# dev-v1_0.net
KiCad netlist of a schematic drawn in EAGLE
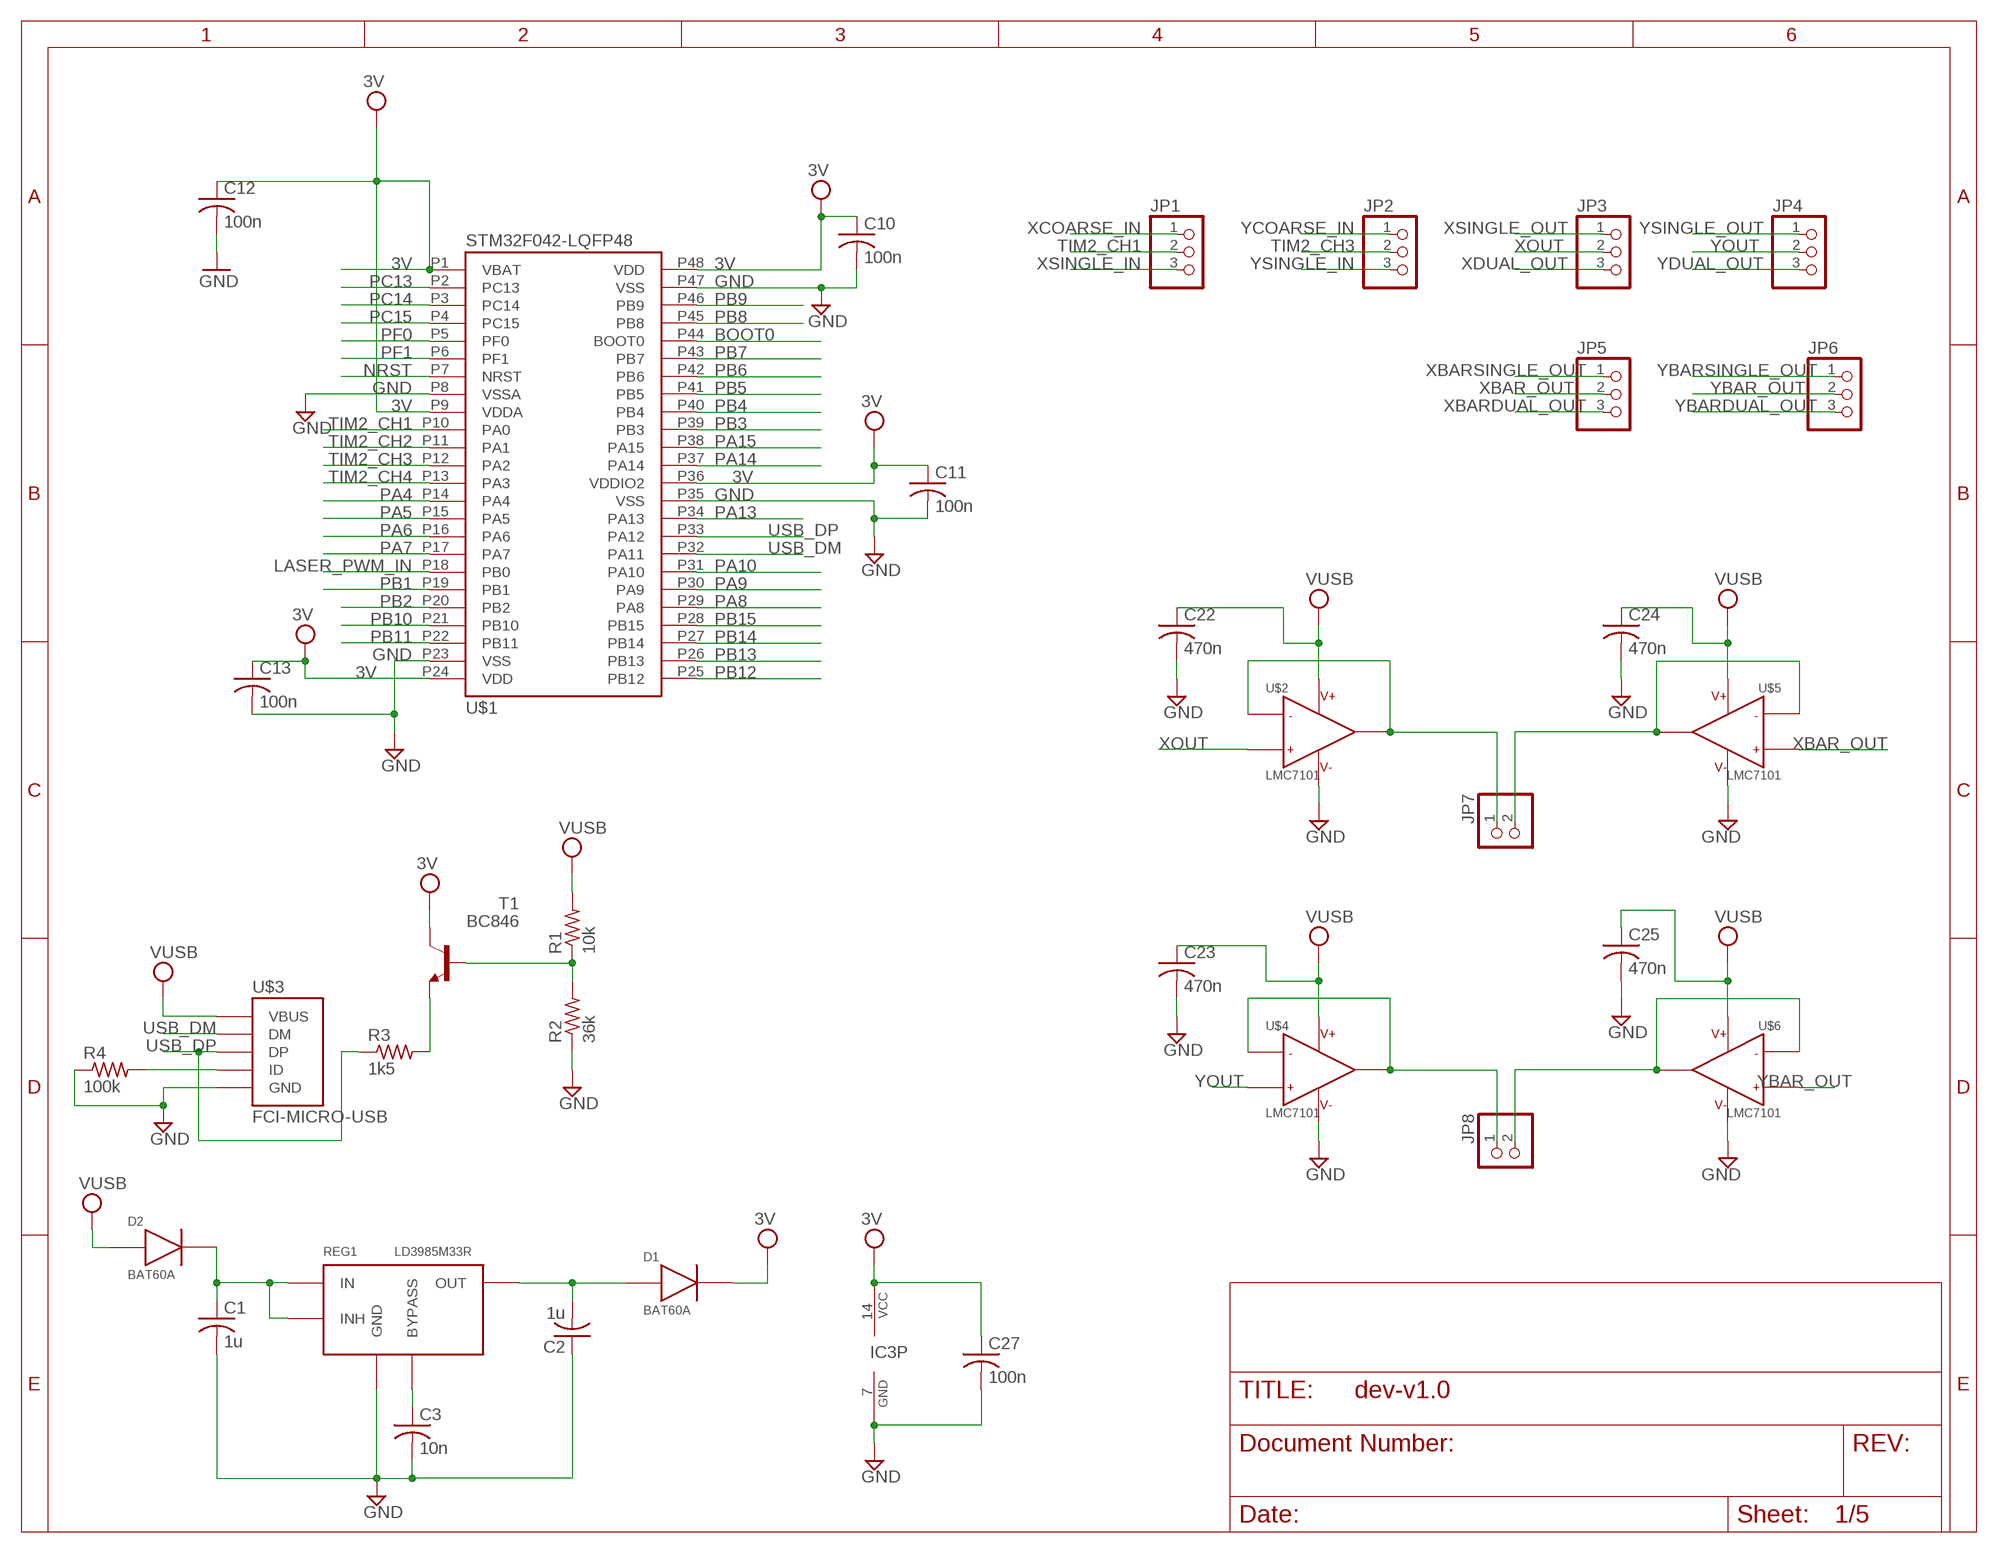
[diagram p0: schematic, sheet 1]
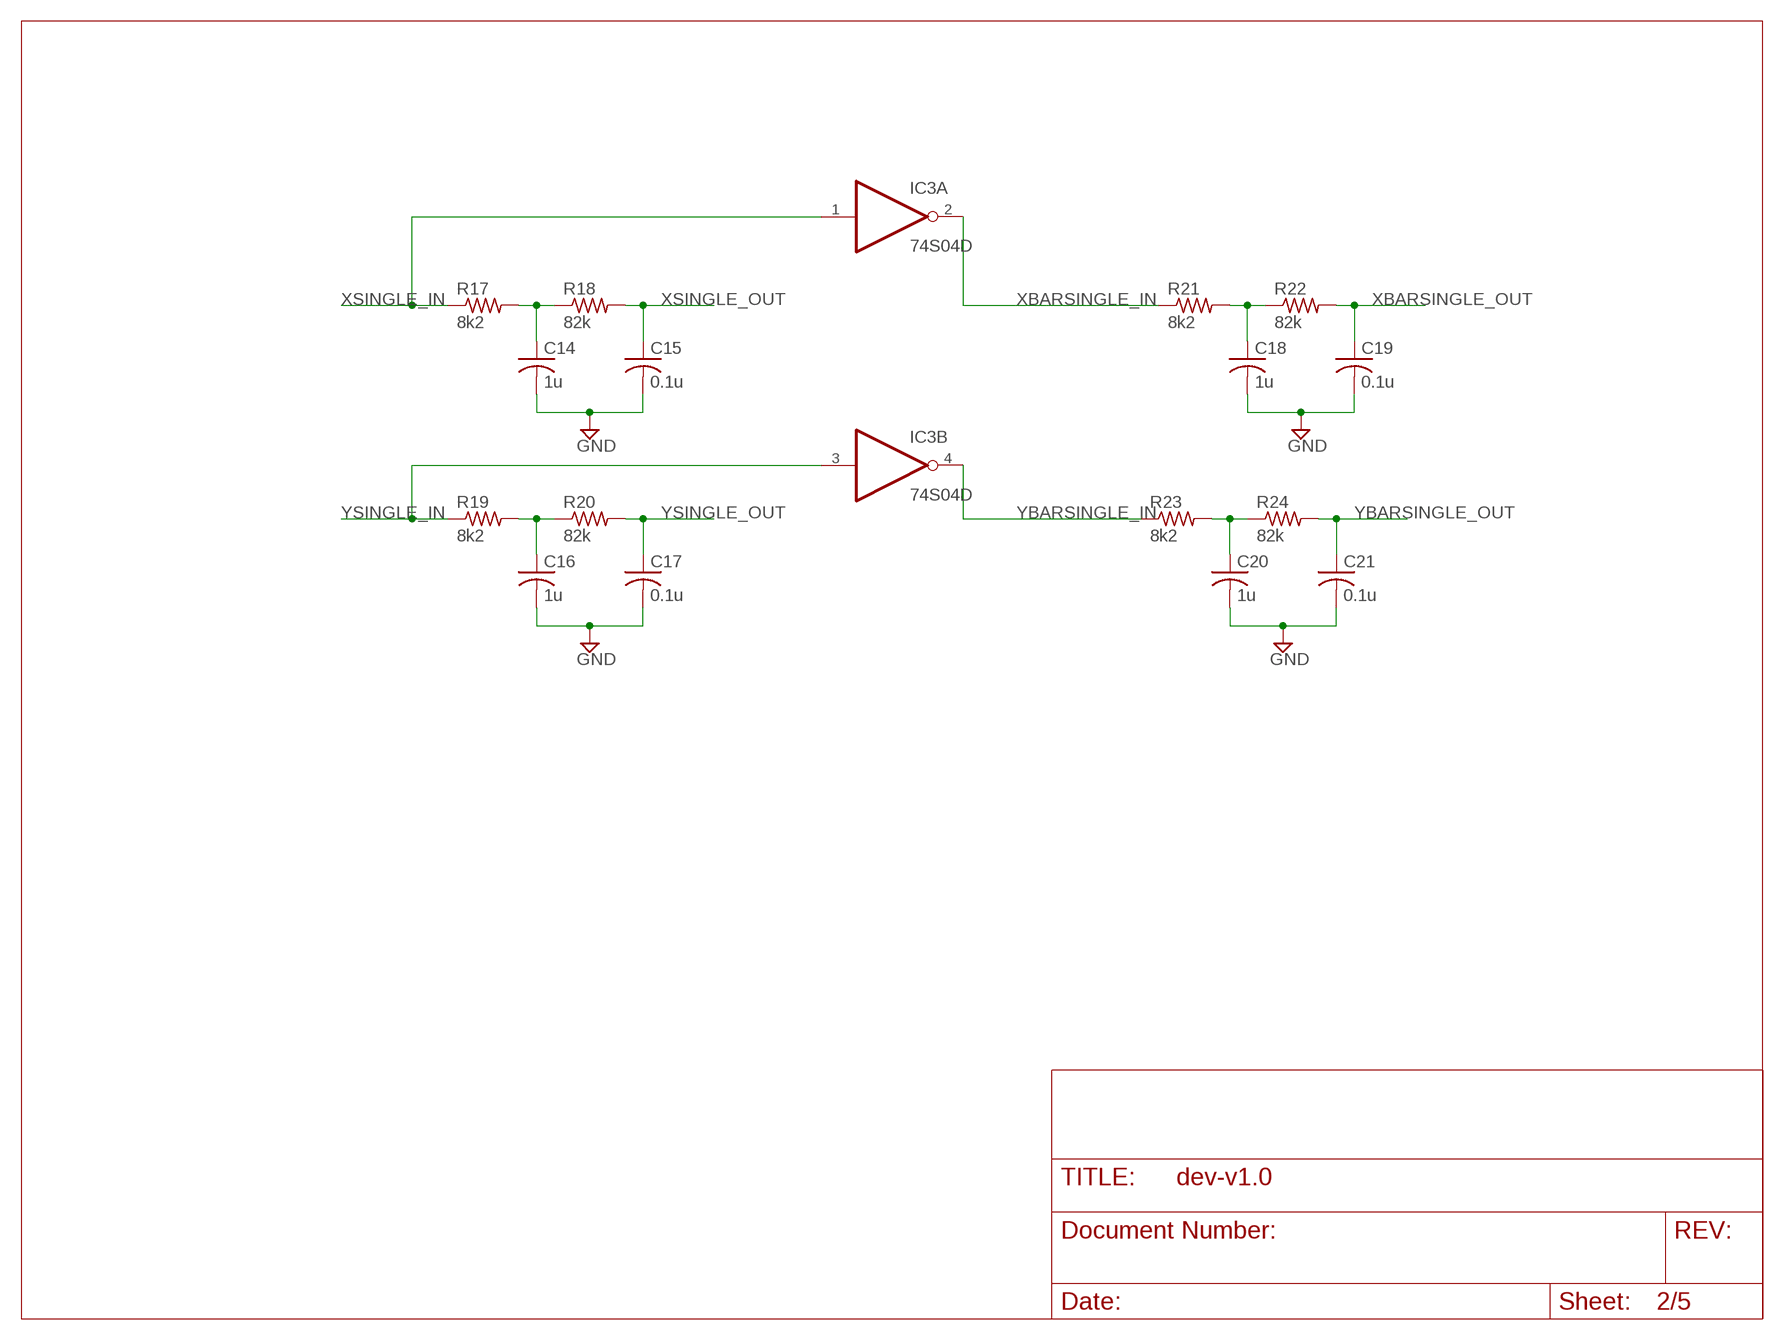
[diagram p1: schematic, sheet 2]
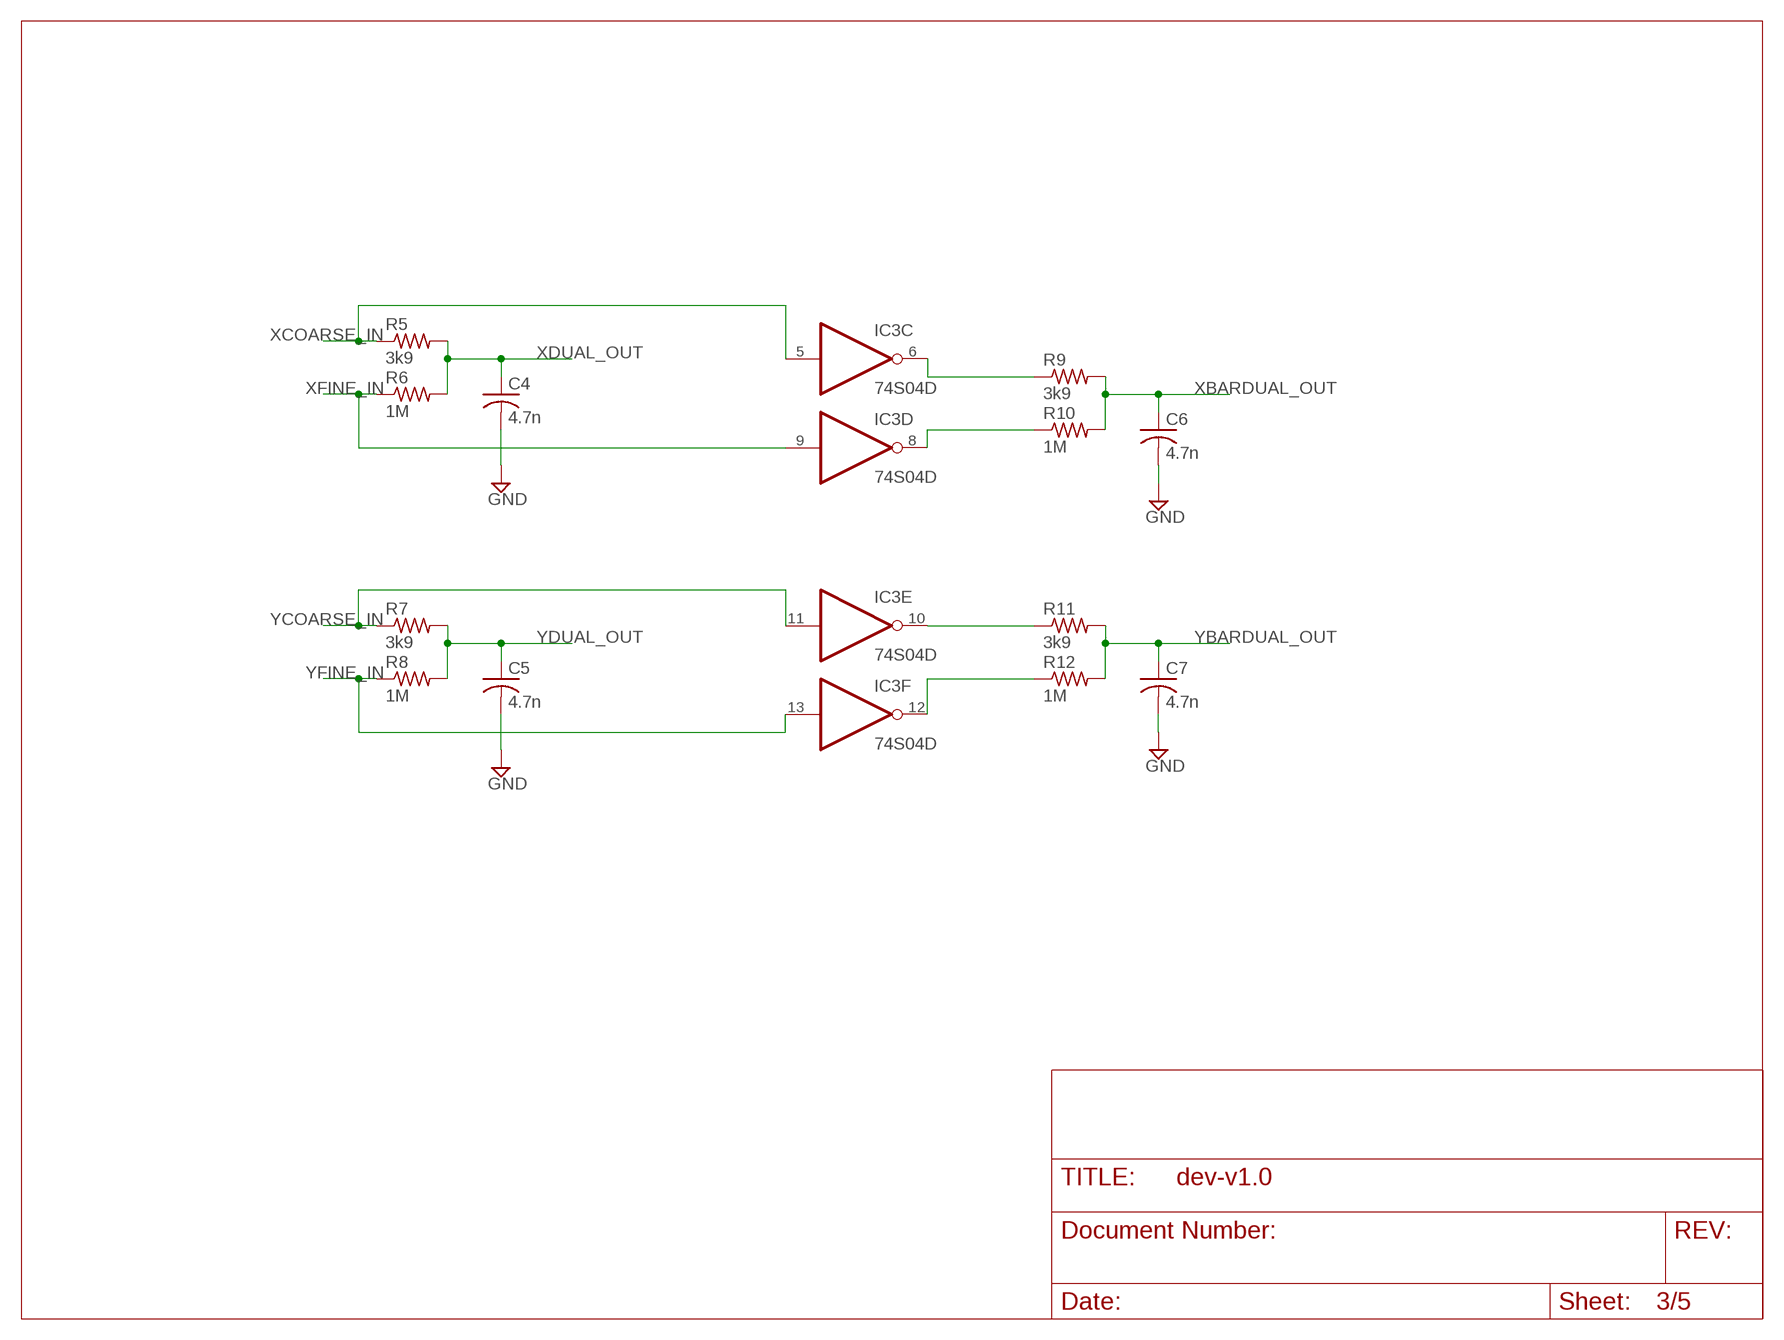
[diagram p2: schematic, sheet 3]
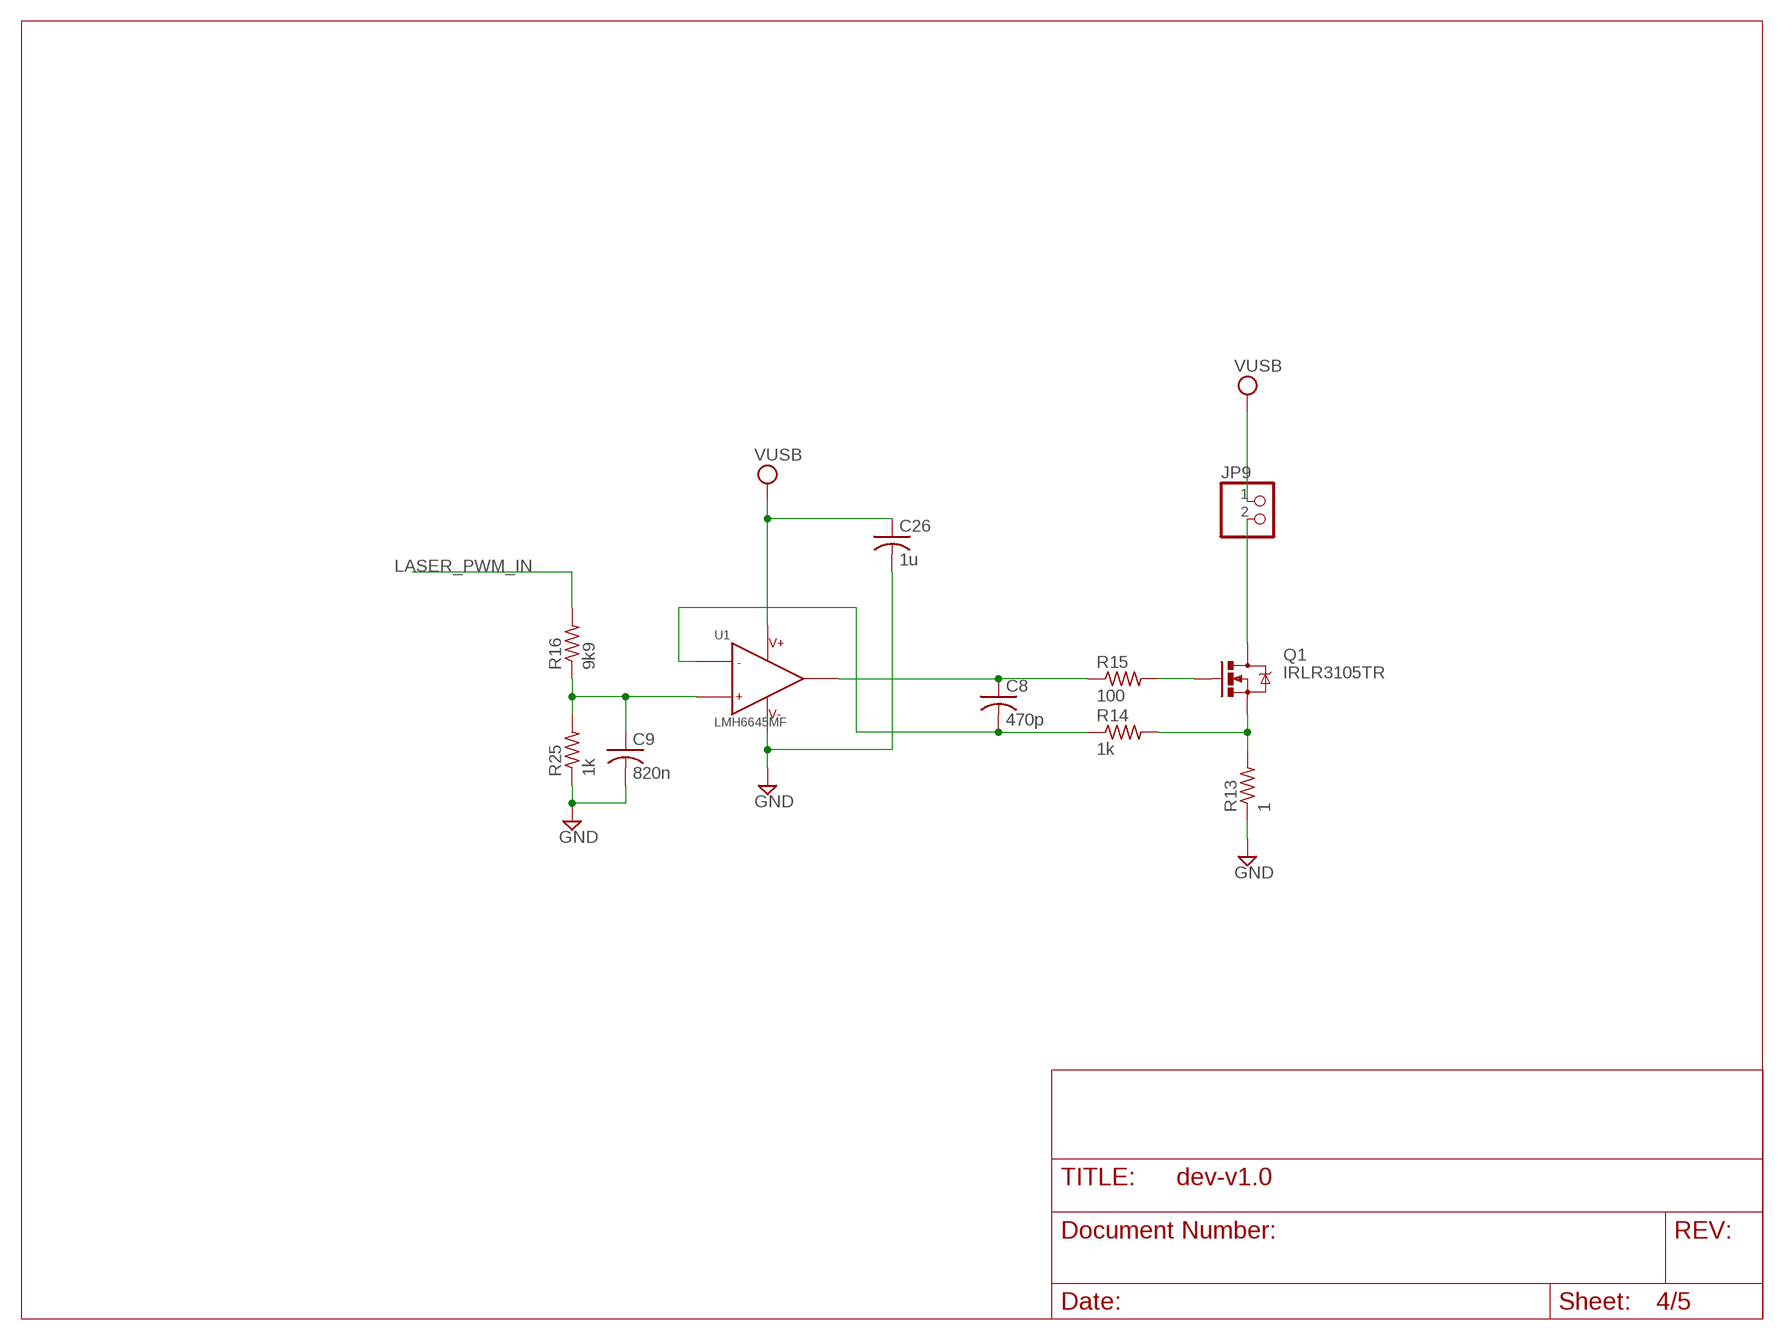
[diagram p3: schematic, sheet 4]
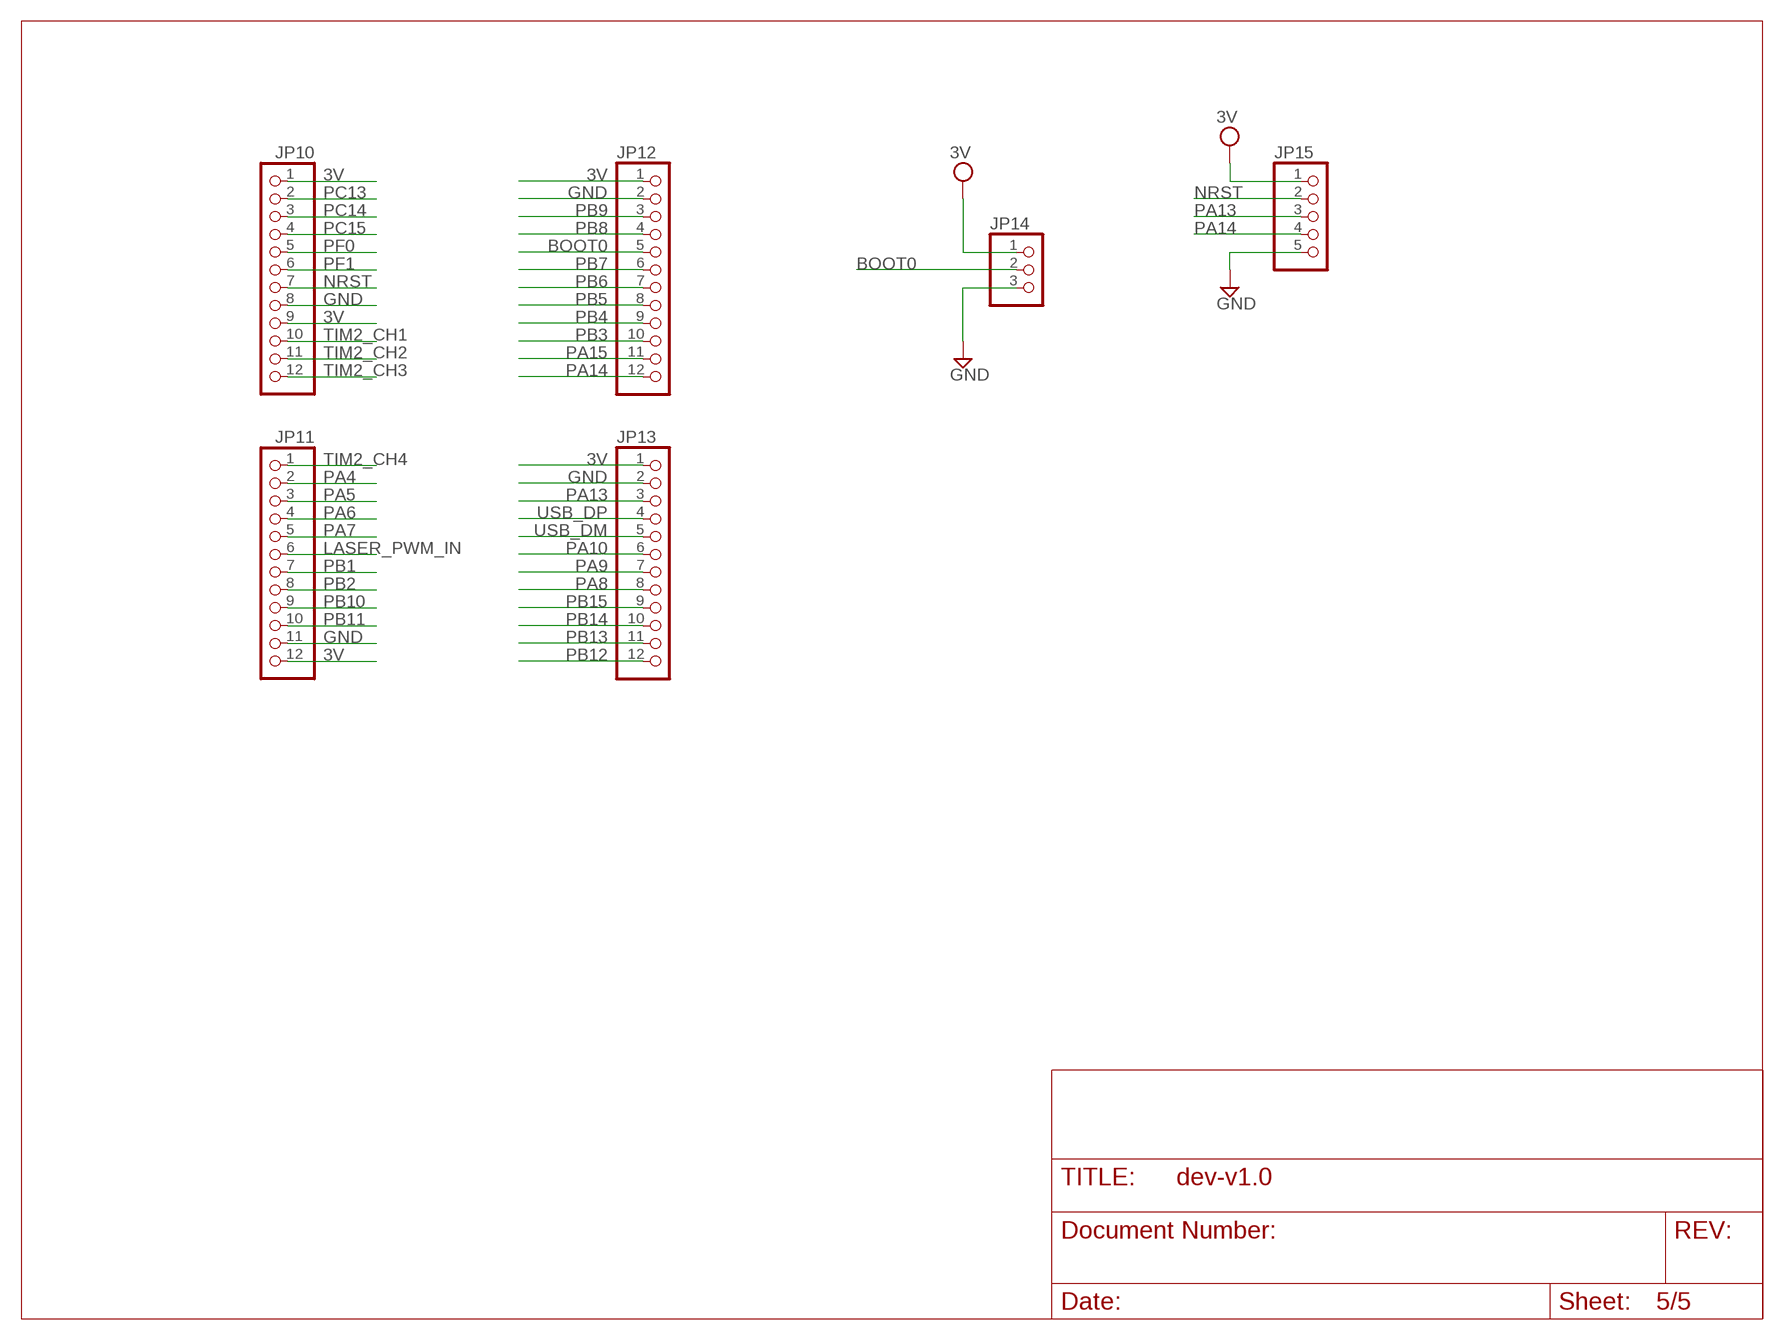
[diagram p4: schematic, sheet 5]

(export (version "E")
  (design (tool "Eeschema 10.0.6"))
  (components
    (comp (ref "C1")
      (value "1u")
      (footprint "eagle-import:C0603")
      (libsource (lib "eagle-import") (part "C-USC0603"))
    )
    (comp (ref "C2")
      (value "1u")
      (footprint "eagle-import:C0603")
      (libsource (lib "eagle-import") (part "C-USC0603"))
    )
    (comp (ref "C3")
      (value "10n")
      (footprint "eagle-import:C0603")
      (libsource (lib "eagle-import") (part "C-USC0603"))
    )
    (comp (ref "C10")
      (value "100n")
      (footprint "eagle-import:C0603")
      (libsource (lib "eagle-import") (part "C-USC0603"))
    )
    (comp (ref "C11")
      (value "100n")
      (footprint "eagle-import:C0603")
      (libsource (lib "eagle-import") (part "C-USC0603"))
    )
    (comp (ref "C12")
      (value "100n")
      (footprint "eagle-import:C0603")
      (libsource (lib "eagle-import") (part "C-USC0603"))
    )
    (comp (ref "C13")
      (value "100n")
      (footprint "eagle-import:C0603")
      (libsource (lib "eagle-import") (part "C-USC0603"))
    )
    (comp (ref "C22")
      (value "470n")
      (footprint "eagle-import:C0603")
      (libsource (lib "eagle-import") (part "C-USC0603"))
    )
    (comp (ref "C23")
      (value "470n")
      (footprint "eagle-import:C0603")
      (libsource (lib "eagle-import") (part "C-USC0603"))
    )
    (comp (ref "C24")
      (value "470n")
      (footprint "eagle-import:C0603")
      (libsource (lib "eagle-import") (part "C-USC0603"))
    )
    (comp (ref "C25")
      (value "470n")
      (footprint "eagle-import:C0603")
      (libsource (lib "eagle-import") (part "C-USC0603"))
    )
    (comp (ref "C27")
      (value "100n")
      (footprint "eagle-import:C0603")
      (libsource (lib "eagle-import") (part "C-USC0603"))
    )
    (comp (ref "D1")
      (value "BAT60A")
      (footprint "eagle-import:SOD323")
      (libsource (lib "eagle-import") (part "BAT60A"))
    )
    (comp (ref "D2")
      (value "BAT60A")
      (footprint "eagle-import:SOD323")
      (libsource (lib "eagle-import") (part "BAT60A"))
    )
    (comp (ref "IC3")
      (value "74S04D")
      (footprint "eagle-import:SO14")
      (libsource (lib "eagle-import") (part "7404DS"))
    )
    (comp (ref "JP1")
      (value "PINHD-1X3")
      (footprint "eagle-import:1X03")
      (libsource (lib "eagle-import") (part "PINHD-1X3"))
    )
    (comp (ref "JP2")
      (value "PINHD-1X3")
      (footprint "eagle-import:1X03")
      (libsource (lib "eagle-import") (part "PINHD-1X3"))
    )
    (comp (ref "JP3")
      (value "PINHD-1X3")
      (footprint "eagle-import:1X03")
      (libsource (lib "eagle-import") (part "PINHD-1X3"))
    )
    (comp (ref "JP4")
      (value "PINHD-1X3")
      (footprint "eagle-import:1X03")
      (libsource (lib "eagle-import") (part "PINHD-1X3"))
    )
    (comp (ref "JP5")
      (value "PINHD-1X3")
      (footprint "eagle-import:1X03")
      (libsource (lib "eagle-import") (part "PINHD-1X3"))
    )
    (comp (ref "JP6")
      (value "PINHD-1X3")
      (footprint "eagle-import:1X03")
      (libsource (lib "eagle-import") (part "PINHD-1X3"))
    )
    (comp (ref "JP7")
      (value "PINHD-1X2")
      (footprint "eagle-import:1X02")
      (libsource (lib "eagle-import") (part "PINHD-1X2"))
    )
    (comp (ref "JP8")
      (value "PINHD-1X2")
      (footprint "eagle-import:1X02")
      (libsource (lib "eagle-import") (part "PINHD-1X2"))
    )
    (comp (ref "R1")
      (value "10k")
      (footprint "eagle-import:R0603")
      (libsource (lib "eagle-import") (part "R-US_R0603"))
    )
    (comp (ref "R2")
      (value "36k")
      (footprint "eagle-import:R0603")
      (libsource (lib "eagle-import") (part "R-US_R0603"))
    )
    (comp (ref "R3")
      (value "1k5")
      (footprint "eagle-import:R0603")
      (libsource (lib "eagle-import") (part "R-US_R0603"))
    )
    (comp (ref "R4")
      (value "100k")
      (footprint "eagle-import:R0603")
      (libsource (lib "eagle-import") (part "R-US_R0603"))
    )
    (comp (ref "REG1")
      (value "LD3985M33R")
      (footprint "eagle-import:SOT23-5L")
      (libsource (lib "eagle-import") (part "LD3985MXXR"))
    )
    (comp (ref "T1")
      (value "BC846")
      (footprint "eagle-import:SOT23")
      (libsource (lib "eagle-import") (part "BC846"))
    )
    (comp (ref "U$1")
      (value "STM32F042-LQFP48")
      (footprint "eagle-import:LQFP48")
      (libsource (lib "eagle-import") (part "STM32F042-LQFP48"))
    )
    (comp (ref "U$2")
      (value "LMC7101")
      (footprint "eagle-import:SOT23-5")
      (libsource (lib "eagle-import") (part "LMC7101"))
    )
    (comp (ref "U$3")
      (value "FCI-MICRO-USB")
      (footprint "eagle-import:FCI-MICROUSB")
      (libsource (lib "eagle-import") (part "FCI-MICRO-USB"))
    )
    (comp (ref "U$4")
      (value "LMC7101")
      (footprint "eagle-import:SOT23-5")
      (libsource (lib "eagle-import") (part "LMC7101"))
    )
    (comp (ref "U$5")
      (value "LMC7101")
      (footprint "eagle-import:SOT23-5")
      (libsource (lib "eagle-import") (part "LMC7101"))
    )
    (comp (ref "U$6")
      (value "LMC7101")
      (footprint "eagle-import:SOT23-5")
      (libsource (lib "eagle-import") (part "LMC7101"))
    )
    (comp (ref "C14")
      (value "1u")
      (footprint "eagle-import:C0603")
      (libsource (lib "eagle-import") (part "C-USC0603"))
    )
    (comp (ref "C15")
      (value "0.1u")
      (footprint "eagle-import:C0603")
      (libsource (lib "eagle-import") (part "C-USC0603"))
    )
    (comp (ref "C16")
      (value "1u")
      (footprint "eagle-import:C0603")
      (libsource (lib "eagle-import") (part "C-USC0603"))
    )
    (comp (ref "C17")
      (value "0.1u")
      (footprint "eagle-import:C0603")
      (libsource (lib "eagle-import") (part "C-USC0603"))
    )
    (comp (ref "C18")
      (value "1u")
      (footprint "eagle-import:C0603")
      (libsource (lib "eagle-import") (part "C-USC0603"))
    )
    (comp (ref "C19")
      (value "0.1u")
      (footprint "eagle-import:C0603")
      (libsource (lib "eagle-import") (part "C-USC0603"))
    )
    (comp (ref "C20")
      (value "1u")
      (footprint "eagle-import:C0603")
      (libsource (lib "eagle-import") (part "C-USC0603"))
    )
    (comp (ref "C21")
      (value "0.1u")
      (footprint "eagle-import:C0603")
      (libsource (lib "eagle-import") (part "C-USC0603"))
    )
    (comp (ref "R17")
      (value "8k2")
      (footprint "eagle-import:R0603")
      (libsource (lib "eagle-import") (part "R-US_R0603"))
    )
    (comp (ref "R18")
      (value "82k")
      (footprint "eagle-import:R0603")
      (libsource (lib "eagle-import") (part "R-US_R0603"))
    )
    (comp (ref "R19")
      (value "8k2")
      (footprint "eagle-import:R0603")
      (libsource (lib "eagle-import") (part "R-US_R0603"))
    )
    (comp (ref "R20")
      (value "82k")
      (footprint "eagle-import:R0603")
      (libsource (lib "eagle-import") (part "R-US_R0603"))
    )
    (comp (ref "R21")
      (value "8k2")
      (footprint "eagle-import:R0603")
      (libsource (lib "eagle-import") (part "R-US_R0603"))
    )
    (comp (ref "R22")
      (value "82k")
      (footprint "eagle-import:R0603")
      (libsource (lib "eagle-import") (part "R-US_R0603"))
    )
    (comp (ref "R23")
      (value "8k2")
      (footprint "eagle-import:R0603")
      (libsource (lib "eagle-import") (part "R-US_R0603"))
    )
    (comp (ref "R24")
      (value "82k")
      (footprint "eagle-import:R0603")
      (libsource (lib "eagle-import") (part "R-US_R0603"))
    )
    (comp (ref "C4")
      (value "4.7n")
      (footprint "eagle-import:C0603")
      (libsource (lib "eagle-import") (part "C-USC0603"))
    )
    (comp (ref "C5")
      (value "4.7n")
      (footprint "eagle-import:C0603")
      (libsource (lib "eagle-import") (part "C-USC0603"))
    )
    (comp (ref "C6")
      (value "4.7n")
      (footprint "eagle-import:C0603")
      (libsource (lib "eagle-import") (part "C-USC0603"))
    )
    (comp (ref "C7")
      (value "4.7n")
      (footprint "eagle-import:C0603")
      (libsource (lib "eagle-import") (part "C-USC0603"))
    )
    (comp (ref "R5")
      (value "3k9")
      (footprint "eagle-import:R0603")
      (libsource (lib "eagle-import") (part "R-US_R0603"))
    )
    (comp (ref "R6")
      (value "1M")
      (footprint "eagle-import:R0603")
      (libsource (lib "eagle-import") (part "R-US_R0603"))
    )
    (comp (ref "R7")
      (value "3k9")
      (footprint "eagle-import:R0603")
      (libsource (lib "eagle-import") (part "R-US_R0603"))
    )
    (comp (ref "R8")
      (value "1M")
      (footprint "eagle-import:R0603")
      (libsource (lib "eagle-import") (part "R-US_R0603"))
    )
    (comp (ref "R9")
      (value "3k9")
      (footprint "eagle-import:R0603")
      (libsource (lib "eagle-import") (part "R-US_R0603"))
    )
    (comp (ref "R10")
      (value "1M")
      (footprint "eagle-import:R0603")
      (libsource (lib "eagle-import") (part "R-US_R0603"))
    )
    (comp (ref "R11")
      (value "3k9")
      (footprint "eagle-import:R0603")
      (libsource (lib "eagle-import") (part "R-US_R0603"))
    )
    (comp (ref "R12")
      (value "1M")
      (footprint "eagle-import:R0603")
      (libsource (lib "eagle-import") (part "R-US_R0603"))
    )
    (comp (ref "JP10")
      (value "PINHD-1X12")
      (footprint "eagle-import:1X12")
      (libsource (lib "eagle-import") (part "PINHD-1X12"))
    )
    (comp (ref "JP11")
      (value "PINHD-1X12")
      (footprint "eagle-import:1X12")
      (libsource (lib "eagle-import") (part "PINHD-1X12"))
    )
    (comp (ref "JP12")
      (value "PINHD-1X12")
      (footprint "eagle-import:1X12")
      (libsource (lib "eagle-import") (part "PINHD-1X12"))
    )
    (comp (ref "JP13")
      (value "PINHD-1X12")
      (footprint "eagle-import:1X12")
      (libsource (lib "eagle-import") (part "PINHD-1X12"))
    )
    (comp (ref "JP14")
      (value "PINHD-1X3")
      (footprint "eagle-import:1X03")
      (libsource (lib "eagle-import") (part "PINHD-1X3"))
    )
    (comp (ref "JP15")
      (value "PINHD-1X5")
      (footprint "eagle-import:1X05")
      (libsource (lib "eagle-import") (part "PINHD-1X5"))
    )
    (comp (ref "C8")
      (value "470p")
      (footprint "eagle-import:C0603")
      (libsource (lib "eagle-import") (part "C-USC0603"))
    )
    (comp (ref "C9")
      (value "820n")
      (footprint "eagle-import:C0603")
      (libsource (lib "eagle-import") (part "C-USC0603"))
    )
    (comp (ref "C26")
      (value "1u")
      (footprint "eagle-import:C0603")
      (libsource (lib "eagle-import") (part "C-USC0603"))
    )
    (comp (ref "JP9")
      (value "PINHD-1X2")
      (footprint "eagle-import:1X02")
      (libsource (lib "eagle-import") (part "PINHD-1X2"))
    )
    (comp (ref "Q1")
      (value "IRLR3105TR")
      (footprint "eagle-import:DPAK")
      (libsource (lib "eagle-import") (part "FET-N-IRLR3105TRIRLR3105TR"))
    )
    (comp (ref "R13")
      (value "1")
      (footprint "eagle-import:R0603")
      (libsource (lib "eagle-import") (part "R-US_R0603"))
    )
    (comp (ref "R14")
      (value "1k")
      (footprint "eagle-import:R0603")
      (libsource (lib "eagle-import") (part "R-US_R0603"))
    )
    (comp (ref "R15")
      (value "100")
      (footprint "eagle-import:R0603")
      (libsource (lib "eagle-import") (part "R-US_R0603"))
    )
    (comp (ref "R16")
      (value "9k9")
      (footprint "eagle-import:R0603")
      (libsource (lib "eagle-import") (part "R-US_R0603"))
    )
    (comp (ref "R25")
      (value "1k")
      (footprint "eagle-import:R0603")
      (libsource (lib "eagle-import") (part "R-US_R0603"))
    )
    (comp (ref "U1")
      (value "LMH6645MF")
      (footprint "eagle-import:SOT23-5")
      (libsource (lib "eagle-import") (part "OPAMP-SINGLELMH6645MF"))
    )
  )
  (nets
    (net (code "1") (name "3V") (class "Default")
      (node (ref "C10") (pin "1") (pinfunction "1_1") (pintype "passive"))
      (node (ref "C11") (pin "1") (pinfunction "1_1") (pintype "passive"))
      (node (ref "C12") (pin "1") (pinfunction "1_1") (pintype "passive"))
      (node (ref "C13") (pin "1") (pinfunction "1_1") (pintype "passive"))
      (node (ref "C27") (pin "1") (pinfunction "1_1") (pintype "passive"))
      (node (ref "D1") (pin "1") (pinfunction "1_1") (pintype "bidirectional"))
      (node (ref "IC3") (pin "14") (pinfunction "VCC_14") (pintype "power_in"))
      (node (ref "JP10") (pin "1") (pinfunction "1_1") (pintype "passive"))
      (node (ref "JP10") (pin "9") (pinfunction "9_9") (pintype "passive"))
      (node (ref "JP11") (pin "12") (pinfunction "12_12") (pintype "passive"))
      (node (ref "JP12") (pin "1") (pinfunction "1_1") (pintype "passive"))
      (node (ref "JP13") (pin "1") (pinfunction "1_1") (pintype "passive"))
      (node (ref "JP14") (pin "1") (pinfunction "1_1") (pintype "passive"))
      (node (ref "JP15") (pin "1") (pinfunction "1_1") (pintype "passive"))
      (node (ref "T1") (pin "3") (pinfunction "C_3") (pintype "passive"))
      (node (ref "U$1") (pin "P1") (pinfunction "VBAT_P1") (pintype "bidirectional"))
      (node (ref "U$1") (pin "P24") (pinfunction "VDD_P24") (pintype "bidirectional"))
      (node (ref "U$1") (pin "P36") (pinfunction "VDDIO2_P36") (pintype "bidirectional"))
      (node (ref "U$1") (pin "P48") (pinfunction "VDD_P48") (pintype "bidirectional"))
      (node (ref "U$1") (pin "P9") (pinfunction "VDDA_P9") (pintype "bidirectional"))
    )
    (net (code "2") (name "BOOT0") (class "Default")
      (node (ref "JP12") (pin "5") (pinfunction "5_5") (pintype "passive"))
      (node (ref "JP14") (pin "2") (pinfunction "2_2") (pintype "passive"))
      (node (ref "U$1") (pin "P44") (pinfunction "BOOT0_P44") (pintype "bidirectional"))
    )
    (net (code "3") (name "GND") (class "Default")
      (node (ref "C1") (pin "2") (pinfunction "2_2") (pintype "passive"))
      (node (ref "C10") (pin "2") (pinfunction "2_2") (pintype "passive"))
      (node (ref "C11") (pin "2") (pinfunction "2_2") (pintype "passive"))
      (node (ref "C12") (pin "2") (pinfunction "2_2") (pintype "passive"))
      (node (ref "C13") (pin "2") (pinfunction "2_2") (pintype "passive"))
      (node (ref "C14") (pin "2") (pinfunction "2_2") (pintype "passive"))
      (node (ref "C15") (pin "2") (pinfunction "2_2") (pintype "passive"))
      (node (ref "C16") (pin "2") (pinfunction "2_2") (pintype "passive"))
      (node (ref "C17") (pin "2") (pinfunction "2_2") (pintype "passive"))
      (node (ref "C18") (pin "2") (pinfunction "2_2") (pintype "passive"))
      (node (ref "C19") (pin "2") (pinfunction "2_2") (pintype "passive"))
      (node (ref "C2") (pin "1") (pinfunction "1_1") (pintype "passive"))
      (node (ref "C20") (pin "2") (pinfunction "2_2") (pintype "passive"))
      (node (ref "C21") (pin "2") (pinfunction "2_2") (pintype "passive"))
      (node (ref "C22") (pin "2") (pinfunction "2_2") (pintype "passive"))
      (node (ref "C23") (pin "2") (pinfunction "2_2") (pintype "passive"))
      (node (ref "C24") (pin "2") (pinfunction "2_2") (pintype "passive"))
      (node (ref "C25") (pin "2") (pinfunction "2_2") (pintype "passive"))
      (node (ref "C26") (pin "2") (pinfunction "2_2") (pintype "passive"))
      (node (ref "C27") (pin "2") (pinfunction "2_2") (pintype "passive"))
      (node (ref "C3") (pin "2") (pinfunction "2_2") (pintype "passive"))
      (node (ref "C4") (pin "2") (pinfunction "2_2") (pintype "passive"))
      (node (ref "C5") (pin "2") (pinfunction "2_2") (pintype "passive"))
      (node (ref "C6") (pin "2") (pinfunction "2_2") (pintype "passive"))
      (node (ref "C7") (pin "2") (pinfunction "2_2") (pintype "passive"))
      (node (ref "C9") (pin "2") (pinfunction "2_2") (pintype "passive"))
      (node (ref "IC3") (pin "7") (pinfunction "GND_7") (pintype "power_in"))
      (node (ref "JP10") (pin "8") (pinfunction "8_8") (pintype "passive"))
      (node (ref "JP11") (pin "11") (pinfunction "11_11") (pintype "passive"))
      (node (ref "JP12") (pin "2") (pinfunction "2_2") (pintype "passive"))
      (node (ref "JP13") (pin "2") (pinfunction "2_2") (pintype "passive"))
      (node (ref "JP14") (pin "3") (pinfunction "3_3") (pintype "passive"))
      (node (ref "JP15") (pin "5") (pinfunction "5_5") (pintype "passive"))
      (node (ref "R13") (pin "1") (pinfunction "1_1") (pintype "passive"))
      (node (ref "R2") (pin "1") (pinfunction "1_1") (pintype "passive"))
      (node (ref "R25") (pin "1") (pinfunction "1_1") (pintype "passive"))
      (node (ref "R4") (pin "1") (pinfunction "1_1") (pintype "passive"))
      (node (ref "REG1") (pin "GND") (pinfunction "GND_GND") (pintype "bidirectional"))
      (node (ref "U$1") (pin "P23") (pinfunction "VSS_P23") (pintype "bidirectional"))
      (node (ref "U$1") (pin "P35") (pinfunction "VSS_P35") (pintype "bidirectional"))
      (node (ref "U$1") (pin "P47") (pinfunction "VSS_P47") (pintype "bidirectional"))
      (node (ref "U$1") (pin "P8") (pinfunction "VSSA_P8") (pintype "bidirectional"))
      (node (ref "U$2") (pin "5") (pinfunction "P5_5") (pintype "power_in"))
      (node (ref "U$3") (pin "P5") (pinfunction "GND_P5") (pintype "bidirectional"))
      (node (ref "U$4") (pin "5") (pinfunction "P5_5") (pintype "power_in"))
      (node (ref "U$5") (pin "5") (pinfunction "P5_5") (pintype "power_in"))
      (node (ref "U$6") (pin "5") (pinfunction "P5_5") (pintype "power_in"))
      (node (ref "U1") (pin "2") (pinfunction "V-_2") (pintype "power_in"))
    )
    (net (code "4") (name "LASER_PWM_IN") (class "Default")
      (node (ref "JP11") (pin "6") (pinfunction "6_6") (pintype "passive"))
      (node (ref "R16") (pin "2") (pinfunction "2_2") (pintype "passive"))
      (node (ref "U$1") (pin "P18") (pinfunction "PB0_P18") (pintype "bidirectional"))
    )
    (net (code "5") (name "NRST") (class "Default")
      (node (ref "JP10") (pin "7") (pinfunction "7_7") (pintype "passive"))
      (node (ref "JP15") (pin "2") (pinfunction "2_2") (pintype "passive"))
      (node (ref "U$1") (pin "P7") (pinfunction "NRST_P7") (pintype "bidirectional"))
    )
    (net (code "6") (name "Net-(C2-Pad2)") (class "Default")
      (node (ref "C2") (pin "2") (pinfunction "2_2") (pintype "passive"))
      (node (ref "D1") (pin "2") (pinfunction "2_2") (pintype "bidirectional"))
      (node (ref "REG1") (pin "OUT") (pinfunction "OUT_OUT") (pintype "bidirectional"))
    )
    (net (code "7") (name "Net-(C3-Pad1)") (class "Default")
      (node (ref "C3") (pin "1") (pinfunction "1_1") (pintype "passive"))
      (node (ref "REG1") (pin "BYPASS") (pinfunction "BYPASS_BYPASS") (pintype "bidirectional"))
    )
    (net (code "8") (name "Net-(C14-Pad1)") (class "Default")
      (node (ref "C14") (pin "1") (pinfunction "1_1") (pintype "passive"))
      (node (ref "R17") (pin "2") (pinfunction "2_2") (pintype "passive"))
      (node (ref "R18") (pin "1") (pinfunction "1_1") (pintype "passive"))
    )
    (net (code "9") (name "Net-(C16-Pad1)") (class "Default")
      (node (ref "C16") (pin "1") (pinfunction "1_1") (pintype "passive"))
      (node (ref "R19") (pin "2") (pinfunction "2_2") (pintype "passive"))
      (node (ref "R20") (pin "1") (pinfunction "1_1") (pintype "passive"))
    )
    (net (code "10") (name "Net-(C18-Pad1)") (class "Default")
      (node (ref "C18") (pin "1") (pinfunction "1_1") (pintype "passive"))
      (node (ref "R21") (pin "2") (pinfunction "2_2") (pintype "passive"))
      (node (ref "R22") (pin "1") (pinfunction "1_1") (pintype "passive"))
    )
    (net (code "11") (name "Net-(C20-Pad1)") (class "Default")
      (node (ref "C20") (pin "1") (pinfunction "1_1") (pintype "passive"))
      (node (ref "R23") (pin "2") (pinfunction "2_2") (pintype "passive"))
      (node (ref "R24") (pin "1") (pinfunction "1_1") (pintype "passive"))
    )
    (net (code "12") (name "Net-(IC3C-O)") (class "Default")
      (node (ref "IC3") (pin "6") (pinfunction "O_6") (pintype "output"))
      (node (ref "R9") (pin "1") (pinfunction "1_1") (pintype "passive"))
    )
    (net (code "13") (name "Net-(IC3D-O)") (class "Default")
      (node (ref "IC3") (pin "8") (pinfunction "O_8") (pintype "output"))
      (node (ref "R10") (pin "1") (pinfunction "1_1") (pintype "passive"))
    )
    (net (code "14") (name "Net-(IC3E-O)") (class "Default")
      (node (ref "IC3") (pin "10") (pinfunction "O_10") (pintype "output"))
      (node (ref "R11") (pin "1") (pinfunction "1_1") (pintype "passive"))
    )
    (net (code "15") (name "Net-(IC3F-O)") (class "Default")
      (node (ref "IC3") (pin "12") (pinfunction "O_12") (pintype "output"))
      (node (ref "R12") (pin "1") (pinfunction "1_1") (pintype "passive"))
    )
    (net (code "16") (name "Net-(Q1-D)") (class "Default")
      (node (ref "JP9") (pin "2") (pinfunction "2_2") (pintype "passive"))
      (node (ref "Q1") (pin "4") (pinfunction "D_4") (pintype "passive"))
    )
    (net (code "17") (name "Net-(Q1-G)") (class "Default")
      (node (ref "Q1") (pin "1") (pinfunction "G_1") (pintype "passive"))
      (node (ref "R15") (pin "2") (pinfunction "2_2") (pintype "passive"))
    )
    (net (code "18") (name "Net-(Q1-S)") (class "Default")
      (node (ref "Q1") (pin "3") (pinfunction "S_3") (pintype "passive"))
      (node (ref "R13") (pin "2") (pinfunction "2_2") (pintype "passive"))
      (node (ref "R14") (pin "2") (pinfunction "2_2") (pintype "passive"))
    )
    (net (code "19") (name "Net-(REG1-INH)") (class "Default")
      (node (ref "C1") (pin "1") (pinfunction "1_1") (pintype "passive"))
      (node (ref "D2") (pin "1") (pinfunction "1_1") (pintype "bidirectional"))
      (node (ref "REG1") (pin "IN") (pinfunction "IN_IN") (pintype "bidirectional"))
      (node (ref "REG1") (pin "INHIBIT") (pinfunction "INH_INHIBIT") (pintype "bidirectional"))
    )
    (net (code "20") (name "Net-(T1-B)") (class "Default")
      (node (ref "R1") (pin "1") (pinfunction "1_1") (pintype "passive"))
      (node (ref "R2") (pin "2") (pinfunction "2_2") (pintype "passive"))
      (node (ref "T1") (pin "1") (pinfunction "B_1") (pintype "passive"))
    )
    (net (code "21") (name "Net-(T1-E)") (class "Default")
      (node (ref "R3") (pin "2") (pinfunction "2_2") (pintype "passive"))
      (node (ref "T1") (pin "2") (pinfunction "E_2") (pintype "passive"))
    )
    (net (code "22") (name "Net-(U$2-P1)") (class "Default")
      (node (ref "JP7") (pin "1") (pinfunction "1_1") (pintype "passive"))
      (node (ref "U$2") (pin "1") (pinfunction "P1_1") (pintype "bidirectional"))
      (node (ref "U$2") (pin "4") (pinfunction "P4_4") (pintype "bidirectional"))
    )
    (net (code "23") (name "Net-(U$3-ID)") (class "Default")
      (node (ref "R4") (pin "2") (pinfunction "2_2") (pintype "passive"))
      (node (ref "U$3") (pin "P4") (pinfunction "ID_P4") (pintype "bidirectional"))
    )
    (net (code "24") (name "Net-(U$4-P1)") (class "Default")
      (node (ref "JP8") (pin "1") (pinfunction "1_1") (pintype "passive"))
      (node (ref "U$4") (pin "1") (pinfunction "P1_1") (pintype "bidirectional"))
      (node (ref "U$4") (pin "4") (pinfunction "P4_4") (pintype "bidirectional"))
    )
    (net (code "25") (name "Net-(U$5-P1)") (class "Default")
      (node (ref "JP7") (pin "2") (pinfunction "2_2") (pintype "passive"))
      (node (ref "U$5") (pin "1") (pinfunction "P1_1") (pintype "bidirectional"))
      (node (ref "U$5") (pin "4") (pinfunction "P4_4") (pintype "bidirectional"))
    )
    (net (code "26") (name "Net-(U$6-P1)") (class "Default")
      (node (ref "JP8") (pin "2") (pinfunction "2_2") (pintype "passive"))
      (node (ref "U$6") (pin "1") (pinfunction "P1_1") (pintype "bidirectional"))
      (node (ref "U$6") (pin "4") (pinfunction "P4_4") (pintype "bidirectional"))
    )
    (net (code "27") (name "Net-(U1-IN+)") (class "Default")
      (node (ref "C9") (pin "1") (pinfunction "1_1") (pintype "passive"))
      (node (ref "R16") (pin "1") (pinfunction "1_1") (pintype "passive"))
      (node (ref "R25") (pin "2") (pinfunction "2_2") (pintype "passive"))
      (node (ref "U1") (pin "3") (pinfunction "IN+_3") (pintype "bidirectional"))
    )
    (net (code "28") (name "Net-(U1-IN-)") (class "Default")
      (node (ref "C8") (pin "2") (pinfunction "2_2") (pintype "passive"))
      (node (ref "R14") (pin "1") (pinfunction "1_1") (pintype "passive"))
      (node (ref "U1") (pin "4") (pinfunction "IN-_4") (pintype "bidirectional"))
    )
    (net (code "29") (name "Net-(U1-OUT)") (class "Default")
      (node (ref "C8") (pin "1") (pinfunction "1_1") (pintype "passive"))
      (node (ref "R15") (pin "1") (pinfunction "1_1") (pintype "passive"))
      (node (ref "U1") (pin "1") (pinfunction "OUT_1") (pintype "bidirectional"))
    )
    (net (code "30") (name "PA4") (class "Default")
      (node (ref "JP11") (pin "2") (pinfunction "2_2") (pintype "passive"))
      (node (ref "U$1") (pin "P14") (pinfunction "PA4_P14") (pintype "bidirectional"))
    )
    (net (code "31") (name "PA5") (class "Default")
      (node (ref "JP11") (pin "3") (pinfunction "3_3") (pintype "passive"))
      (node (ref "U$1") (pin "P15") (pinfunction "PA5_P15") (pintype "bidirectional"))
    )
    (net (code "32") (name "PA6") (class "Default")
      (node (ref "JP11") (pin "4") (pinfunction "4_4") (pintype "passive"))
      (node (ref "U$1") (pin "P16") (pinfunction "PA6_P16") (pintype "bidirectional"))
    )
    (net (code "33") (name "PA7") (class "Default")
      (node (ref "JP11") (pin "5") (pinfunction "5_5") (pintype "passive"))
      (node (ref "U$1") (pin "P17") (pinfunction "PA7_P17") (pintype "bidirectional"))
    )
    (net (code "34") (name "PA8") (class "Default")
      (node (ref "JP13") (pin "8") (pinfunction "8_8") (pintype "passive"))
      (node (ref "U$1") (pin "P29") (pinfunction "PA8_P29") (pintype "bidirectional"))
    )
    (net (code "35") (name "PA9") (class "Default")
      (node (ref "JP13") (pin "7") (pinfunction "7_7") (pintype "passive"))
      (node (ref "U$1") (pin "P30") (pinfunction "PA9_P30") (pintype "bidirectional"))
    )
    (net (code "36") (name "PA10") (class "Default")
      (node (ref "JP13") (pin "6") (pinfunction "6_6") (pintype "passive"))
      (node (ref "U$1") (pin "P31") (pinfunction "PA10_P31") (pintype "bidirectional"))
    )
    (net (code "37") (name "PA13") (class "Default")
      (node (ref "JP13") (pin "3") (pinfunction "3_3") (pintype "passive"))
      (node (ref "JP15") (pin "3") (pinfunction "3_3") (pintype "passive"))
      (node (ref "U$1") (pin "P34") (pinfunction "PA13_P34") (pintype "bidirectional"))
    )
    (net (code "38") (name "PA14") (class "Default")
      (node (ref "JP12") (pin "12") (pinfunction "12_12") (pintype "passive"))
      (node (ref "JP15") (pin "4") (pinfunction "4_4") (pintype "passive"))
      (node (ref "U$1") (pin "P37") (pinfunction "PA14_P37") (pintype "bidirectional"))
    )
    (net (code "39") (name "PA15") (class "Default")
      (node (ref "JP12") (pin "11") (pinfunction "11_11") (pintype "passive"))
      (node (ref "U$1") (pin "P38") (pinfunction "PA15_P38") (pintype "bidirectional"))
    )
    (net (code "40") (name "PB1") (class "Default")
      (node (ref "JP11") (pin "7") (pinfunction "7_7") (pintype "passive"))
      (node (ref "U$1") (pin "P19") (pinfunction "PB1_P19") (pintype "bidirectional"))
    )
    (net (code "41") (name "PB2") (class "Default")
      (node (ref "JP11") (pin "8") (pinfunction "8_8") (pintype "passive"))
      (node (ref "U$1") (pin "P20") (pinfunction "PB2_P20") (pintype "bidirectional"))
    )
    (net (code "42") (name "PB3") (class "Default")
      (node (ref "JP12") (pin "10") (pinfunction "10_10") (pintype "passive"))
      (node (ref "U$1") (pin "P39") (pinfunction "PB3_P39") (pintype "bidirectional"))
    )
    (net (code "43") (name "PB4") (class "Default")
      (node (ref "JP12") (pin "9") (pinfunction "9_9") (pintype "passive"))
      (node (ref "U$1") (pin "P40") (pinfunction "PB4_P40") (pintype "bidirectional"))
    )
    (net (code "44") (name "PB5") (class "Default")
      (node (ref "JP12") (pin "8") (pinfunction "8_8") (pintype "passive"))
      (node (ref "U$1") (pin "P41") (pinfunction "PB5_P41") (pintype "bidirectional"))
    )
    (net (code "45") (name "PB6") (class "Default")
      (node (ref "JP12") (pin "7") (pinfunction "7_7") (pintype "passive"))
      (node (ref "U$1") (pin "P42") (pinfunction "PB6_P42") (pintype "bidirectional"))
    )
    (net (code "46") (name "PB7") (class "Default")
      (node (ref "JP12") (pin "6") (pinfunction "6_6") (pintype "passive"))
      (node (ref "U$1") (pin "P43") (pinfunction "PB7_P43") (pintype "bidirectional"))
    )
    (net (code "47") (name "PB8") (class "Default")
      (node (ref "JP12") (pin "4") (pinfunction "4_4") (pintype "passive"))
      (node (ref "U$1") (pin "P45") (pinfunction "PB8_P45") (pintype "bidirectional"))
    )
    (net (code "48") (name "PB9") (class "Default")
      (node (ref "JP12") (pin "3") (pinfunction "3_3") (pintype "passive"))
      (node (ref "U$1") (pin "P46") (pinfunction "PB9_P46") (pintype "bidirectional"))
    )
    (net (code "49") (name "PB10") (class "Default")
      (node (ref "JP11") (pin "9") (pinfunction "9_9") (pintype "passive"))
      (node (ref "U$1") (pin "P21") (pinfunction "PB10_P21") (pintype "bidirectional"))
    )
    (net (code "50") (name "PB11") (class "Default")
      (node (ref "JP11") (pin "10") (pinfunction "10_10") (pintype "passive"))
      (node (ref "U$1") (pin "P22") (pinfunction "PB11_P22") (pintype "bidirectional"))
    )
    (net (code "51") (name "PB12") (class "Default")
      (node (ref "JP13") (pin "12") (pinfunction "12_12") (pintype "passive"))
      (node (ref "U$1") (pin "P25") (pinfunction "PB12_P25") (pintype "bidirectional"))
    )
    (net (code "52") (name "PB13") (class "Default")
      (node (ref "JP13") (pin "11") (pinfunction "11_11") (pintype "passive"))
      (node (ref "U$1") (pin "P26") (pinfunction "PB13_P26") (pintype "bidirectional"))
    )
    (net (code "53") (name "PB14") (class "Default")
      (node (ref "JP13") (pin "10") (pinfunction "10_10") (pintype "passive"))
      (node (ref "U$1") (pin "P27") (pinfunction "PB14_P27") (pintype "bidirectional"))
    )
    (net (code "54") (name "PB15") (class "Default")
      (node (ref "JP13") (pin "9") (pinfunction "9_9") (pintype "passive"))
      (node (ref "U$1") (pin "P28") (pinfunction "PB15_P28") (pintype "bidirectional"))
    )
    (net (code "55") (name "PC13") (class "Default")
      (node (ref "JP10") (pin "2") (pinfunction "2_2") (pintype "passive"))
      (node (ref "U$1") (pin "P2") (pinfunction "PC13_P2") (pintype "bidirectional"))
    )
    (net (code "56") (name "PC14") (class "Default")
      (node (ref "JP10") (pin "3") (pinfunction "3_3") (pintype "passive"))
      (node (ref "U$1") (pin "P3") (pinfunction "PC14_P3") (pintype "bidirectional"))
    )
    (net (code "57") (name "PC15") (class "Default")
      (node (ref "JP10") (pin "4") (pinfunction "4_4") (pintype "passive"))
      (node (ref "U$1") (pin "P4") (pinfunction "PC15_P4") (pintype "bidirectional"))
    )
    (net (code "58") (name "PF0") (class "Default")
      (node (ref "JP10") (pin "5") (pinfunction "5_5") (pintype "passive"))
      (node (ref "U$1") (pin "P5") (pinfunction "PF0_P5") (pintype "bidirectional"))
    )
    (net (code "59") (name "PF1") (class "Default")
      (node (ref "JP10") (pin "6") (pinfunction "6_6") (pintype "passive"))
      (node (ref "U$1") (pin "P6") (pinfunction "PF1_P6") (pintype "bidirectional"))
    )
    (net (code "60") (name "TIM2_CH1") (class "Default")
      (node (ref "JP1") (pin "2") (pinfunction "2_2") (pintype "passive"))
      (node (ref "JP10") (pin "10") (pinfunction "10_10") (pintype "passive"))
      (node (ref "U$1") (pin "P10") (pinfunction "PA0_P10") (pintype "bidirectional"))
    )
    (net (code "61") (name "TIM2_CH2") (class "Default")
      (node (ref "JP10") (pin "11") (pinfunction "11_11") (pintype "passive"))
      (node (ref "U$1") (pin "P11") (pinfunction "PA1_P11") (pintype "bidirectional"))
    )
    (net (code "62") (name "TIM2_CH3") (class "Default")
      (node (ref "JP10") (pin "12") (pinfunction "12_12") (pintype "passive"))
      (node (ref "JP2") (pin "2") (pinfunction "2_2") (pintype "passive"))
      (node (ref "U$1") (pin "P12") (pinfunction "PA2_P12") (pintype "bidirectional"))
    )
    (net (code "63") (name "TIM2_CH4") (class "Default")
      (node (ref "JP11") (pin "1") (pinfunction "1_1") (pintype "passive"))
      (node (ref "U$1") (pin "P13") (pinfunction "PA3_P13") (pintype "bidirectional"))
    )
    (net (code "64") (name "USB_DM") (class "Default")
      (node (ref "JP13") (pin "5") (pinfunction "5_5") (pintype "passive"))
      (node (ref "U$1") (pin "P32") (pinfunction "PA11_P32") (pintype "bidirectional"))
      (node (ref "U$3") (pin "P2") (pinfunction "DM_P2") (pintype "bidirectional"))
    )
    (net (code "65") (name "USB_DP") (class "Default")
      (node (ref "JP13") (pin "4") (pinfunction "4_4") (pintype "passive"))
      (node (ref "R3") (pin "1") (pinfunction "1_1") (pintype "passive"))
      (node (ref "U$1") (pin "P33") (pinfunction "PA12_P33") (pintype "bidirectional"))
      (node (ref "U$3") (pin "P3") (pinfunction "DP_P3") (pintype "bidirectional"))
    )
    (net (code "66") (name "VUSB") (class "Default")
      (node (ref "C22") (pin "1") (pinfunction "1_1") (pintype "passive"))
      (node (ref "C23") (pin "1") (pinfunction "1_1") (pintype "passive"))
      (node (ref "C24") (pin "1") (pinfunction "1_1") (pintype "passive"))
      (node (ref "C25") (pin "1") (pinfunction "1_1") (pintype "passive"))
      (node (ref "C26") (pin "1") (pinfunction "1_1") (pintype "passive"))
      (node (ref "D2") (pin "2") (pinfunction "2_2") (pintype "bidirectional"))
      (node (ref "JP9") (pin "1") (pinfunction "1_1") (pintype "passive"))
      (node (ref "R1") (pin "2") (pinfunction "2_2") (pintype "passive"))
      (node (ref "U$2") (pin "2") (pinfunction "P2_2") (pintype "power_in"))
      (node (ref "U$3") (pin "P1") (pinfunction "VBUS_P1") (pintype "bidirectional"))
      (node (ref "U$4") (pin "2") (pinfunction "P2_2") (pintype "power_in"))
      (node (ref "U$5") (pin "2") (pinfunction "P2_2") (pintype "power_in"))
      (node (ref "U$6") (pin "2") (pinfunction "P2_2") (pintype "power_in"))
      (node (ref "U1") (pin "5") (pinfunction "V+_5") (pintype "power_in"))
    )
    (net (code "67") (name "XBARDUAL_OUT") (class "Default")
      (node (ref "C6") (pin "1") (pinfunction "1_1") (pintype "passive"))
      (node (ref "JP5") (pin "3") (pinfunction "3_3") (pintype "passive"))
      (node (ref "R10") (pin "2") (pinfunction "2_2") (pintype "passive"))
      (node (ref "R9") (pin "2") (pinfunction "2_2") (pintype "passive"))
    )
    (net (code "68") (name "XBARSINGLE_IN") (class "Default")
      (node (ref "IC3") (pin "2") (pinfunction "O_2") (pintype "output"))
      (node (ref "R21") (pin "1") (pinfunction "1_1") (pintype "passive"))
    )
    (net (code "69") (name "XBARSINGLE_OUT") (class "Default")
      (node (ref "C19") (pin "1") (pinfunction "1_1") (pintype "passive"))
      (node (ref "JP5") (pin "1") (pinfunction "1_1") (pintype "passive"))
      (node (ref "R22") (pin "2") (pinfunction "2_2") (pintype "passive"))
    )
    (net (code "70") (name "XBAR_OUT") (class "Default")
      (node (ref "JP5") (pin "2") (pinfunction "2_2") (pintype "passive"))
      (node (ref "U$5") (pin "3") (pinfunction "P3_3") (pintype "bidirectional"))
    )
    (net (code "71") (name "XCOARSE_IN") (class "Default")
      (node (ref "IC3") (pin "5") (pinfunction "I_5") (pintype "input"))
      (node (ref "JP1") (pin "1") (pinfunction "1_1") (pintype "passive"))
      (node (ref "R5") (pin "1") (pinfunction "1_1") (pintype "passive"))
    )
    (net (code "72") (name "XDUAL_OUT") (class "Default")
      (node (ref "C4") (pin "1") (pinfunction "1_1") (pintype "passive"))
      (node (ref "JP3") (pin "3") (pinfunction "3_3") (pintype "passive"))
      (node (ref "R5") (pin "2") (pinfunction "2_2") (pintype "passive"))
      (node (ref "R6") (pin "2") (pinfunction "2_2") (pintype "passive"))
    )
    (net (code "73") (name "XFINE_IN") (class "Default")
      (node (ref "IC3") (pin "9") (pinfunction "I_9") (pintype "input"))
      (node (ref "R6") (pin "1") (pinfunction "1_1") (pintype "passive"))
    )
    (net (code "74") (name "XOUT") (class "Default")
      (node (ref "JP3") (pin "2") (pinfunction "2_2") (pintype "passive"))
      (node (ref "U$2") (pin "3") (pinfunction "P3_3") (pintype "bidirectional"))
    )
    (net (code "75") (name "XSINGLE_IN") (class "Default")
      (node (ref "IC3") (pin "1") (pinfunction "I_1") (pintype "input"))
      (node (ref "JP1") (pin "3") (pinfunction "3_3") (pintype "passive"))
      (node (ref "R17") (pin "1") (pinfunction "1_1") (pintype "passive"))
    )
    (net (code "76") (name "XSINGLE_OUT") (class "Default")
      (node (ref "C15") (pin "1") (pinfunction "1_1") (pintype "passive"))
      (node (ref "JP3") (pin "1") (pinfunction "1_1") (pintype "passive"))
      (node (ref "R18") (pin "2") (pinfunction "2_2") (pintype "passive"))
    )
    (net (code "77") (name "YBARDUAL_OUT") (class "Default")
      (node (ref "C7") (pin "1") (pinfunction "1_1") (pintype "passive"))
      (node (ref "JP6") (pin "3") (pinfunction "3_3") (pintype "passive"))
      (node (ref "R11") (pin "2") (pinfunction "2_2") (pintype "passive"))
      (node (ref "R12") (pin "2") (pinfunction "2_2") (pintype "passive"))
    )
    (net (code "78") (name "YBARSINGLE_IN") (class "Default")
      (node (ref "IC3") (pin "4") (pinfunction "O_4") (pintype "output"))
      (node (ref "R23") (pin "1") (pinfunction "1_1") (pintype "passive"))
    )
    (net (code "79") (name "YBARSINGLE_OUT") (class "Default")
      (node (ref "C21") (pin "1") (pinfunction "1_1") (pintype "passive"))
      (node (ref "JP6") (pin "1") (pinfunction "1_1") (pintype "passive"))
      (node (ref "R24") (pin "2") (pinfunction "2_2") (pintype "passive"))
    )
    (net (code "80") (name "YBAR_OUT") (class "Default")
      (node (ref "JP6") (pin "2") (pinfunction "2_2") (pintype "passive"))
      (node (ref "U$6") (pin "3") (pinfunction "P3_3") (pintype "bidirectional"))
    )
    (net (code "81") (name "YCOARSE_IN") (class "Default")
      (node (ref "IC3") (pin "11") (pinfunction "I_11") (pintype "input"))
      (node (ref "JP2") (pin "1") (pinfunction "1_1") (pintype "passive"))
      (node (ref "R7") (pin "1") (pinfunction "1_1") (pintype "passive"))
    )
    (net (code "82") (name "YDUAL_OUT") (class "Default")
      (node (ref "C5") (pin "1") (pinfunction "1_1") (pintype "passive"))
      (node (ref "JP4") (pin "3") (pinfunction "3_3") (pintype "passive"))
      (node (ref "R7") (pin "2") (pinfunction "2_2") (pintype "passive"))
      (node (ref "R8") (pin "2") (pinfunction "2_2") (pintype "passive"))
    )
    (net (code "83") (name "YFINE_IN") (class "Default")
      (node (ref "IC3") (pin "13") (pinfunction "I_13") (pintype "input"))
      (node (ref "R8") (pin "1") (pinfunction "1_1") (pintype "passive"))
    )
    (net (code "84") (name "YOUT") (class "Default")
      (node (ref "JP4") (pin "2") (pinfunction "2_2") (pintype "passive"))
      (node (ref "U$4") (pin "3") (pinfunction "P3_3") (pintype "bidirectional"))
    )
    (net (code "85") (name "YSINGLE_IN") (class "Default")
      (node (ref "IC3") (pin "3") (pinfunction "I_3") (pintype "input"))
      (node (ref "JP2") (pin "3") (pinfunction "3_3") (pintype "passive"))
      (node (ref "R19") (pin "1") (pinfunction "1_1") (pintype "passive"))
    )
    (net (code "86") (name "YSINGLE_OUT") (class "Default")
      (node (ref "C17") (pin "1") (pinfunction "1_1") (pintype "passive"))
      (node (ref "JP4") (pin "1") (pinfunction "1_1") (pintype "passive"))
      (node (ref "R20") (pin "2") (pinfunction "2_2") (pintype "passive"))
    )
  )
)
